# SCH_Pico-slide-show-2_2025-06-19.net
KiCad netlist of a schematic drawn in EasyEDA
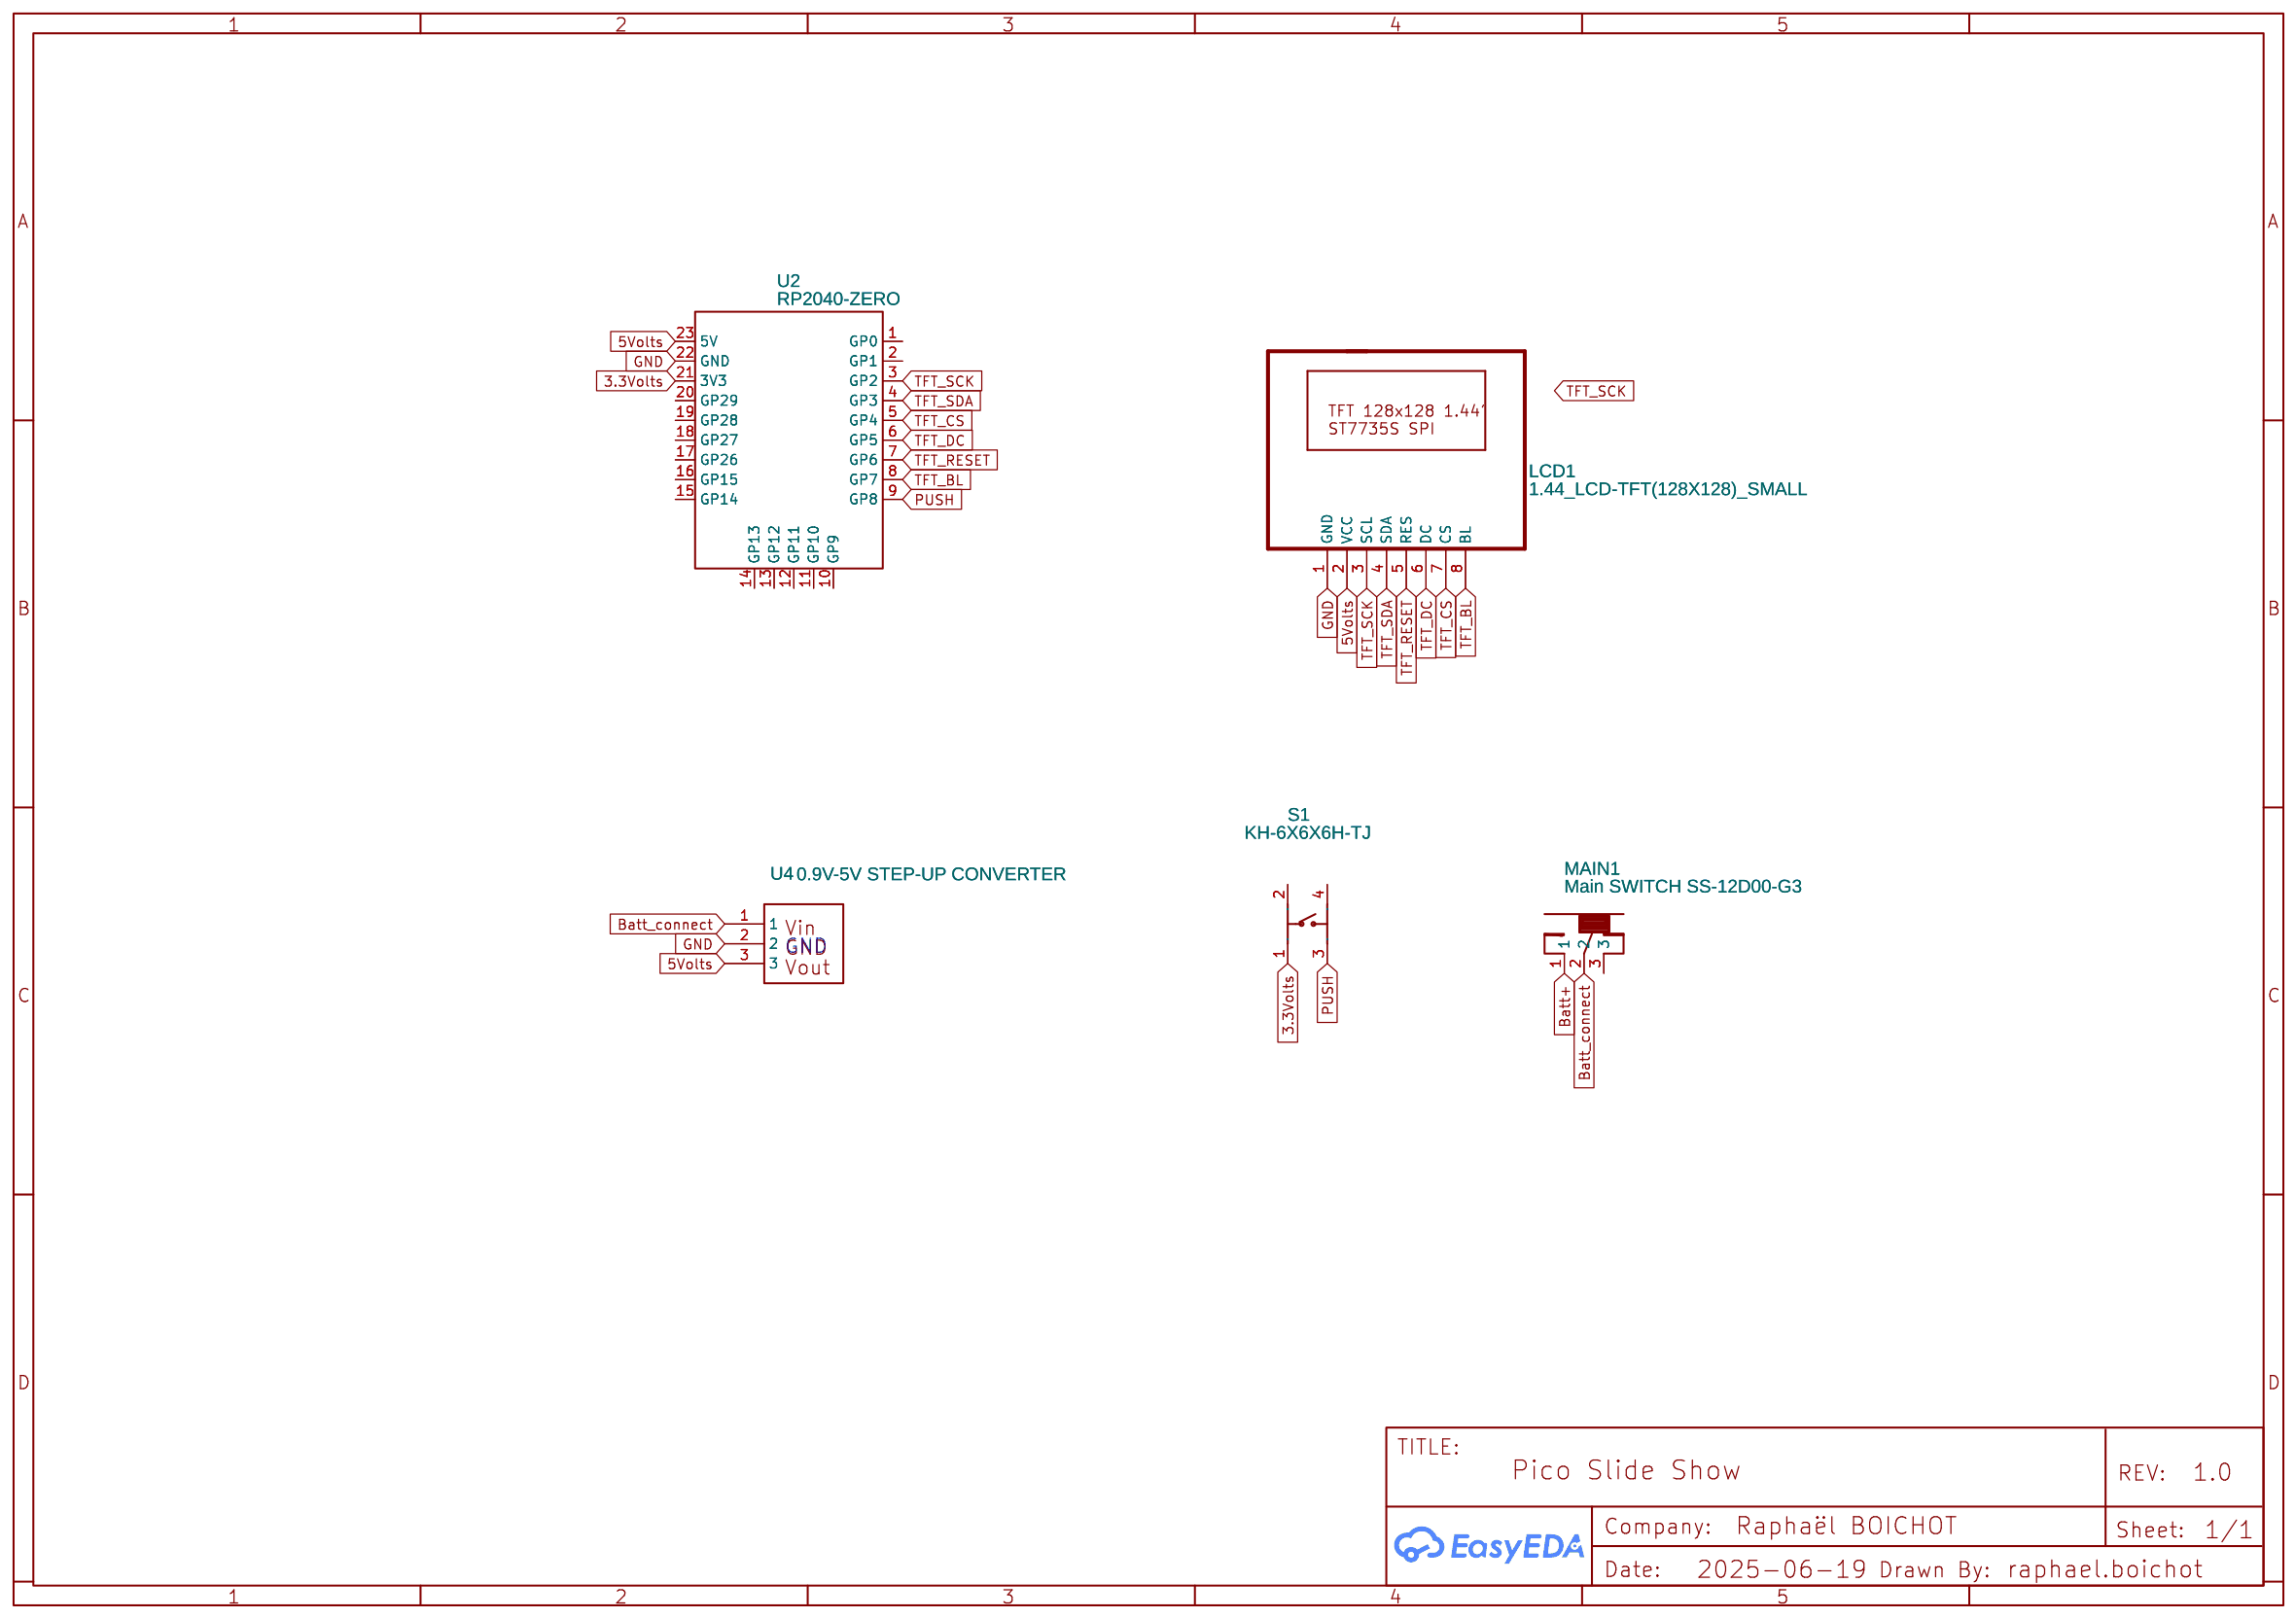
[diagram p0: schematic sheet]

(export (version "E")
  (design (tool "Eeschema 10.0.6"))
  (components
    (comp (ref "LCD1")
      (value "1.44_LCD-TFT(128X128)_SMALL")
      (libsource (lib "") (part "1.44_LCD-TFT(128X128)_SMALL"))
    )
    (comp (ref "MAIN1")
      (value "Main SWITCH SS-12D00-G3")
      (fields
        (field (name "Manufacturer Part") "TOGGLE SWITCH SS-12D00-G3")
        (field (name "Manufacturer") "Dailywell")
      )
      (libsource (lib "") (part "TOGGLE SWITCH SS-12D00-G3"))
    )
    (comp (ref "S1")
      (value "KH-6X6X6H-TJ")
      (fields (field (name "Manufacturer") "kinghelm(金航标)"))
      (libsource (lib "") (part "KH-6X6X6H-TJ"))
    )
    (comp (ref "U2") (value "RP2040-ZERO") (libsource (lib "") (part "RP2040-ZERO")))
    (comp (ref "U4")
      (value "0.9V-5V STEP-UP CONVERTER")
      (fields (field (name "Manufacturer") "Generic"))
      (libsource (lib "") (part "0.9V-5V STEP-UP CONVERTER"))
    )
  )
  (nets
    (net (code "1") (name "3.3Volts") (class "Default")
      (node (ref "S1") (pin "1") (pinfunction "1_1") (pintype "unspecified"))
      (node (ref "U2") (pin "21") (pinfunction "3V3_21") (pintype "unspecified"))
    )
    (net (code "2") (name "5Volts") (class "Default")
      (node (ref "LCD1") (pin "2") (pinfunction "VCC_2") (pintype "output"))
      (node (ref "U2") (pin "23") (pinfunction "5V_23") (pintype "unspecified"))
      (node (ref "U4") (pin "3") (pinfunction "3_3") (pintype "unspecified"))
    )
    (net (code "3") (name "Batt+") (class "Default")
      (node (ref "MAIN1") (pin "1") (pinfunction "1_1") (pintype "bidirectional"))
    )
    (net (code "4") (name "Batt_connect") (class "Default")
      (node (ref "MAIN1") (pin "2") (pinfunction "2_2") (pintype "bidirectional"))
      (node (ref "U4") (pin "1") (pinfunction "1_1") (pintype "unspecified"))
    )
    (net (code "5") (name "GND") (class "Default")
      (node (ref "LCD1") (pin "1") (pinfunction "GND_1") (pintype "passive"))
      (node (ref "U2") (pin "22") (pinfunction "GND_22") (pintype "unspecified"))
      (node (ref "U4") (pin "2") (pinfunction "2_2") (pintype "unspecified"))
    )
    (net (code "6") (name "PUSH") (class "Default")
      (node (ref "S1") (pin "3") (pinfunction "3_3") (pintype "unspecified"))
      (node (ref "U2") (pin "9") (pinfunction "GP8_9") (pintype "unspecified"))
    )
    (net (code "7") (name "TFT_BL") (class "Default")
      (node (ref "LCD1") (pin "8") (pinfunction "BL_8") (pintype "input"))
      (node (ref "U2") (pin "8") (pinfunction "GP7_8") (pintype "unspecified"))
    )
    (net (code "8") (name "TFT_CS") (class "Default")
      (node (ref "LCD1") (pin "7") (pinfunction "CS_7") (pintype "unspecified"))
      (node (ref "U2") (pin "5") (pinfunction "GP4_5") (pintype "unspecified"))
    )
    (net (code "9") (name "TFT_DC") (class "Default")
      (node (ref "LCD1") (pin "6") (pinfunction "DC_6") (pintype "input"))
      (node (ref "U2") (pin "6") (pinfunction "GP5_6") (pintype "unspecified"))
    )
    (net (code "10") (name "TFT_RESET") (class "Default")
      (node (ref "LCD1") (pin "5") (pinfunction "RES_5") (pintype "input"))
      (node (ref "U2") (pin "7") (pinfunction "GP6_7") (pintype "unspecified"))
    )
    (net (code "11") (name "TFT_SCK") (class "Default")
      (node (ref "LCD1") (pin "3") (pinfunction "SCL_3") (pintype "input"))
      (node (ref "U2") (pin "3") (pinfunction "GP2_3") (pintype "unspecified"))
    )
    (net (code "12") (name "TFT_SDA") (class "Default")
      (node (ref "LCD1") (pin "4") (pinfunction "SDA_4") (pintype "input"))
      (node (ref "U2") (pin "4") (pinfunction "GP3_4") (pintype "unspecified"))
    )
    (net (code "13") (name "unconnected-(MAIN1-Pad3)") (class "Default")
      (node (ref "MAIN1") (pin "3") (pinfunction "3_3") (pintype "unspecified"))
    )
    (net (code "14") (name "unconnected-(S1-Pad2)") (class "Default")
      (node (ref "S1") (pin "2") (pinfunction "2_2") (pintype "unspecified"))
    )
    (net (code "15") (name "unconnected-(S1-Pad4)") (class "Default")
      (node (ref "S1") (pin "4") (pinfunction "4_4") (pintype "unspecified"))
    )
    (net (code "16") (name "unconnected-(U2-GP0-Pad1)") (class "Default")
      (node (ref "U2") (pin "1") (pinfunction "GP0_1") (pintype "unspecified"))
    )
    (net (code "17") (name "unconnected-(U2-GP1-Pad2)") (class "Default")
      (node (ref "U2") (pin "2") (pinfunction "GP1_2") (pintype "unspecified"))
    )
    (net (code "18") (name "unconnected-(U2-GP9-Pad10)") (class "Default")
      (node (ref "U2") (pin "10") (pinfunction "GP9_10") (pintype "unspecified"))
    )
    (net (code "19") (name "unconnected-(U2-GP10-Pad11)") (class "Default")
      (node (ref "U2") (pin "11") (pinfunction "GP10_11") (pintype "unspecified"))
    )
    (net (code "20") (name "unconnected-(U2-GP11-Pad12)") (class "Default")
      (node (ref "U2") (pin "12") (pinfunction "GP11_12") (pintype "unspecified"))
    )
    (net (code "21") (name "unconnected-(U2-GP12-Pad13)") (class "Default")
      (node (ref "U2") (pin "13") (pinfunction "GP12_13") (pintype "unspecified"))
    )
    (net (code "22") (name "unconnected-(U2-GP13-Pad14)") (class "Default")
      (node (ref "U2") (pin "14") (pinfunction "GP13_14") (pintype "unspecified"))
    )
    (net (code "23") (name "unconnected-(U2-GP14-Pad15)") (class "Default")
      (node (ref "U2") (pin "15") (pinfunction "GP14_15") (pintype "unspecified"))
    )
    (net (code "24") (name "unconnected-(U2-GP15-Pad16)") (class "Default")
      (node (ref "U2") (pin "16") (pinfunction "GP15_16") (pintype "unspecified"))
    )
    (net (code "25") (name "unconnected-(U2-GP26-Pad17)") (class "Default")
      (node (ref "U2") (pin "17") (pinfunction "GP26_17") (pintype "unspecified"))
    )
    (net (code "26") (name "unconnected-(U2-GP27-Pad18)") (class "Default")
      (node (ref "U2") (pin "18") (pinfunction "GP27_18") (pintype "unspecified"))
    )
    (net (code "27") (name "unconnected-(U2-GP28-Pad19)") (class "Default")
      (node (ref "U2") (pin "19") (pinfunction "GP28_19") (pintype "unspecified"))
    )
    (net (code "28") (name "unconnected-(U2-GP29-Pad20)") (class "Default")
      (node (ref "U2") (pin "20") (pinfunction "GP29_20") (pintype "unspecified"))
    )
  )
)
